# LCD.net
KiCad netlist of a schematic drawn in Altium Designer
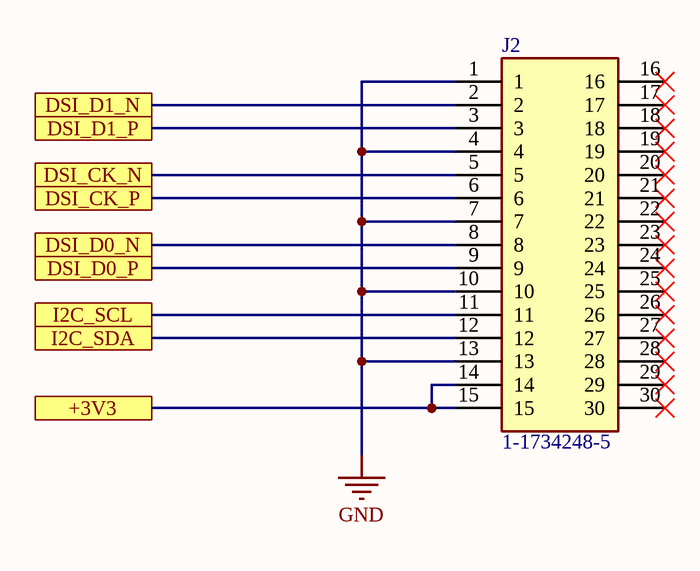
[diagram p0: LCD.SchDoc]

(export (version "E")
  (design (tool "Eeschema 10.0.6"))
  (components
    (comp (ref "J2")
      (value "1-1734248-5")
      (footprint "SamacSys:117342485")
      (description "Connector")
      (fields (field (name "MOUSER PART NUMBER") "571-1-1734248-5"))
      (libsource (lib "*") (part "1-1734248-5"))
    )
  )
  (nets
    (net (code "1") (name "/+3V3") (class "Default")
      (node (ref "J2") (pin "14") (pinfunction "14_14") (pintype "passive"))
      (node (ref "J2") (pin "15") (pinfunction "15_15") (pintype "passive"))
    )
    (net (code "2") (name "/DSI_CK_N") (class "Default")
      (node (ref "J2") (pin "5") (pinfunction "5_5") (pintype "passive"))
    )
    (net (code "3") (name "/DSI_CK_P") (class "Default")
      (node (ref "J2") (pin "6") (pinfunction "6_6") (pintype "passive"))
    )
    (net (code "4") (name "/DSI_D0_N") (class "Default")
      (node (ref "J2") (pin "8") (pinfunction "8_8") (pintype "passive"))
    )
    (net (code "5") (name "/DSI_D0_P") (class "Default")
      (node (ref "J2") (pin "9") (pinfunction "9_9") (pintype "passive"))
    )
    (net (code "6") (name "/DSI_D1_N") (class "Default")
      (node (ref "J2") (pin "2") (pinfunction "2_2") (pintype "passive"))
    )
    (net (code "7") (name "/DSI_D1_P") (class "Default")
      (node (ref "J2") (pin "3") (pinfunction "3_3") (pintype "passive"))
    )
    (net (code "8") (name "/I2C_SCL") (class "Default")
      (node (ref "J2") (pin "11") (pinfunction "11_11") (pintype "passive"))
    )
    (net (code "9") (name "/I2C_SDA") (class "Default")
      (node (ref "J2") (pin "12") (pinfunction "12_12") (pintype "passive"))
    )
    (net (code "10") (name "GND") (class "Default")
      (node (ref "J2") (pin "1") (pinfunction "1_1") (pintype "passive"))
      (node (ref "J2") (pin "10") (pinfunction "10_10") (pintype "passive"))
      (node (ref "J2") (pin "13") (pinfunction "13_13") (pintype "passive"))
      (node (ref "J2") (pin "4") (pinfunction "4_4") (pintype "passive"))
      (node (ref "J2") (pin "7") (pinfunction "7_7") (pintype "passive"))
    )
    (net (code "11") (name "unconnected-(J2-Pad16)") (class "Default")
      (node (ref "J2") (pin "16") (pinfunction "16_16") (pintype "passive+no_connect"))
    )
    (net (code "12") (name "unconnected-(J2-Pad17)") (class "Default")
      (node (ref "J2") (pin "17") (pinfunction "17_17") (pintype "passive+no_connect"))
    )
    (net (code "13") (name "unconnected-(J2-Pad18)") (class "Default")
      (node (ref "J2") (pin "18") (pinfunction "18_18") (pintype "passive+no_connect"))
    )
    (net (code "14") (name "unconnected-(J2-Pad19)") (class "Default")
      (node (ref "J2") (pin "19") (pinfunction "19_19") (pintype "passive+no_connect"))
    )
    (net (code "15") (name "unconnected-(J2-Pad20)") (class "Default")
      (node (ref "J2") (pin "20") (pinfunction "20_20") (pintype "passive+no_connect"))
    )
    (net (code "16") (name "unconnected-(J2-Pad21)") (class "Default")
      (node (ref "J2") (pin "21") (pinfunction "21_21") (pintype "passive+no_connect"))
    )
    (net (code "17") (name "unconnected-(J2-Pad22)") (class "Default")
      (node (ref "J2") (pin "22") (pinfunction "22_22") (pintype "passive+no_connect"))
    )
    (net (code "18") (name "unconnected-(J2-Pad23)") (class "Default")
      (node (ref "J2") (pin "23") (pinfunction "23_23") (pintype "passive+no_connect"))
    )
    (net (code "19") (name "unconnected-(J2-Pad24)") (class "Default")
      (node (ref "J2") (pin "24") (pinfunction "24_24") (pintype "passive+no_connect"))
    )
    (net (code "20") (name "unconnected-(J2-Pad25)") (class "Default")
      (node (ref "J2") (pin "25") (pinfunction "25_25") (pintype "passive+no_connect"))
    )
    (net (code "21") (name "unconnected-(J2-Pad26)") (class "Default")
      (node (ref "J2") (pin "26") (pinfunction "26_26") (pintype "passive+no_connect"))
    )
    (net (code "22") (name "unconnected-(J2-Pad27)") (class "Default")
      (node (ref "J2") (pin "27") (pinfunction "27_27") (pintype "passive+no_connect"))
    )
    (net (code "23") (name "unconnected-(J2-Pad28)") (class "Default")
      (node (ref "J2") (pin "28") (pinfunction "28_28") (pintype "passive+no_connect"))
    )
    (net (code "24") (name "unconnected-(J2-Pad29)") (class "Default")
      (node (ref "J2") (pin "29") (pinfunction "29_29") (pintype "passive+no_connect"))
    )
    (net (code "25") (name "unconnected-(J2-Pad30)") (class "Default")
      (node (ref "J2") (pin "30") (pinfunction "30_30") (pintype "passive+no_connect"))
    )
  )
)
